# Power.net
KiCad netlist of a schematic drawn in Altium Designer
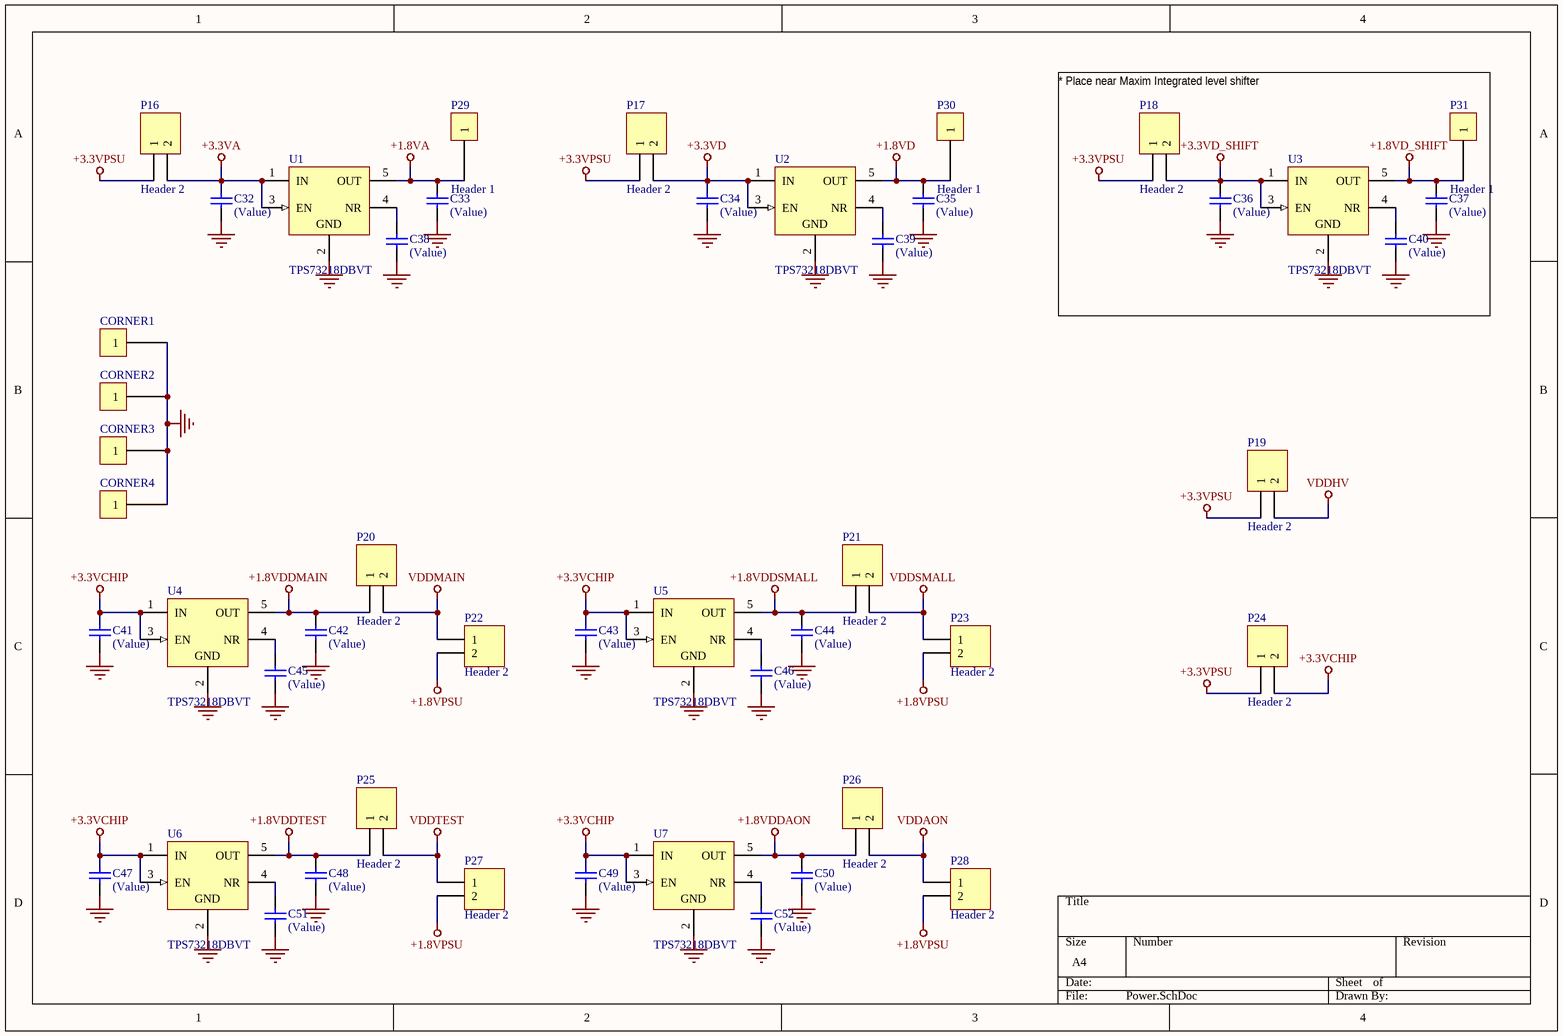
[diagram p0: Power.SchDoc]

(export (version "E")
  (design (tool "Eeschema 10.0.6"))
  (components
    (comp (ref "C32")
      (value "(Value)")
      (footprint "CAPC1608X90X35ML10T15")
      (description "0603")
      (fields (field (name "MANUFACTURER") "Murata"))
      (libsource (lib "Altium Content Vault") (part "CAP-NP-2"))
    )
    (comp (ref "C33")
      (value "(Value)")
      (footprint "CAPC1608X90X35ML10T15")
      (description "0603")
      (fields (field (name "MANUFACTURER") "Murata"))
      (libsource (lib "Altium Content Vault") (part "CAP-NP-2"))
    )
    (comp (ref "C34")
      (value "(Value)")
      (footprint "CAPC1608X90X35ML10T15")
      (description "0603")
      (fields (field (name "MANUFACTURER") "Murata"))
      (libsource (lib "Altium Content Vault") (part "CAP-NP-2"))
    )
    (comp (ref "C35")
      (value "(Value)")
      (footprint "CAPC1608X90X35ML10T15")
      (description "0603")
      (fields (field (name "MANUFACTURER") "Murata"))
      (libsource (lib "Altium Content Vault") (part "CAP-NP-2"))
    )
    (comp (ref "C36")
      (value "(Value)")
      (footprint "CAPC1608X90X35ML10T15")
      (description "0603")
      (fields (field (name "MANUFACTURER") "Murata"))
      (libsource (lib "Altium Content Vault") (part "CAP-NP-2"))
    )
    (comp (ref "C37")
      (value "(Value)")
      (footprint "CAPC1608X90X35ML10T15")
      (description "0603")
      (fields (field (name "MANUFACTURER") "Murata"))
      (libsource (lib "Altium Content Vault") (part "CAP-NP-2"))
    )
    (comp (ref "C38")
      (value "(Value)")
      (footprint "CAPC1608X90X35ML10T15")
      (description "0603")
      (fields (field (name "MANUFACTURER") "Murata"))
      (libsource (lib "Altium Content Vault") (part "CAP-NP-2"))
    )
    (comp (ref "C39")
      (value "(Value)")
      (footprint "CAPC1608X90X35ML10T15")
      (description "0603")
      (fields (field (name "MANUFACTURER") "Murata"))
      (libsource (lib "Altium Content Vault") (part "CAP-NP-2"))
    )
    (comp (ref "C40")
      (value "(Value)")
      (footprint "CAPC1608X90X35ML10T15")
      (description "0603")
      (fields (field (name "MANUFACTURER") "Murata"))
      (libsource (lib "Altium Content Vault") (part "CAP-NP-2"))
    )
    (comp (ref "C41")
      (value "(Value)")
      (footprint "CAPC1608X90X35ML10T15")
      (description "0603")
      (fields (field (name "MANUFACTURER") "Murata"))
      (libsource (lib "Altium Content Vault") (part "CAP-NP-2"))
    )
    (comp (ref "C42")
      (value "(Value)")
      (footprint "CAPC1608X90X35ML10T15")
      (description "0603")
      (fields (field (name "MANUFACTURER") "Murata"))
      (libsource (lib "Altium Content Vault") (part "CAP-NP-2"))
    )
    (comp (ref "C43")
      (value "(Value)")
      (footprint "CAPC1608X90X35ML10T15")
      (description "0603")
      (fields (field (name "MANUFACTURER") "Murata"))
      (libsource (lib "Altium Content Vault") (part "CAP-NP-2"))
    )
    (comp (ref "C44")
      (value "(Value)")
      (footprint "CAPC1608X90X35ML10T15")
      (description "0603")
      (fields (field (name "MANUFACTURER") "Murata"))
      (libsource (lib "Altium Content Vault") (part "CAP-NP-2"))
    )
    (comp (ref "C45")
      (value "(Value)")
      (footprint "CAPC1608X90X35ML10T15")
      (description "0603")
      (fields (field (name "MANUFACTURER") "Murata"))
      (libsource (lib "Altium Content Vault") (part "CAP-NP-2"))
    )
    (comp (ref "C46")
      (value "(Value)")
      (footprint "CAPC1608X90X35ML10T15")
      (description "0603")
      (fields (field (name "MANUFACTURER") "Murata"))
      (libsource (lib "Altium Content Vault") (part "CAP-NP-2"))
    )
    (comp (ref "C47")
      (value "(Value)")
      (footprint "CAPC1608X90X35ML10T15")
      (description "0603")
      (fields (field (name "MANUFACTURER") "Murata"))
      (libsource (lib "Altium Content Vault") (part "CAP-NP-2"))
    )
    (comp (ref "C48")
      (value "(Value)")
      (footprint "CAPC1608X90X35ML10T15")
      (description "0603")
      (fields (field (name "MANUFACTURER") "Murata"))
      (libsource (lib "Altium Content Vault") (part "CAP-NP-2"))
    )
    (comp (ref "C49")
      (value "(Value)")
      (footprint "CAPC1608X90X35ML10T15")
      (description "0603")
      (fields (field (name "MANUFACTURER") "Murata"))
      (libsource (lib "Altium Content Vault") (part "CAP-NP-2"))
    )
    (comp (ref "C50")
      (value "(Value)")
      (footprint "CAPC1608X90X35ML10T15")
      (description "0603")
      (fields (field (name "MANUFACTURER") "Murata"))
      (libsource (lib "Altium Content Vault") (part "CAP-NP-2"))
    )
    (comp (ref "C51")
      (value "(Value)")
      (footprint "CAPC1608X90X35ML10T15")
      (description "0603")
      (fields (field (name "MANUFACTURER") "Murata"))
      (libsource (lib "Altium Content Vault") (part "CAP-NP-2"))
    )
    (comp (ref "C52")
      (value "(Value)")
      (footprint "CAPC1608X90X35ML10T15")
      (description "0603")
      (fields (field (name "MANUFACTURER") "Murata"))
      (libsource (lib "Altium Content Vault") (part "CAP-NP-2"))
    )
    (comp (ref "CORNER1")
      (value "Corner Mount")
      (footprint "CornerMount")
      (libsource (lib "intlib") (part "Corner Mount"))
    )
    (comp (ref "CORNER2")
      (value "Corner Mount")
      (footprint "CornerMount")
      (libsource (lib "intlib") (part "Corner Mount"))
    )
    (comp (ref "CORNER3")
      (value "Corner Mount")
      (footprint "CornerMount")
      (libsource (lib "intlib") (part "Corner Mount"))
    )
    (comp (ref "CORNER4")
      (value "Corner Mount")
      (footprint "CornerMount")
      (libsource (lib "intlib") (part "Corner Mount"))
    )
    (comp (ref "P16")
      (value "Header 2")
      (footprint "HDR1X2")
      (description "Header, 2-Pin")
      (fields (field (name "PUBLISHER") "Altium Limited"))
      (libsource (lib "Miscellaneous Connectors") (part "Header 2"))
    )
    (comp (ref "P17")
      (value "Header 2")
      (footprint "HDR1X2")
      (description "Header, 2-Pin")
      (fields (field (name "PUBLISHER") "Altium Limited"))
      (libsource (lib "Miscellaneous Connectors") (part "Header 2"))
    )
    (comp (ref "P18")
      (value "Header 2")
      (footprint "HDR1X2")
      (description "Header, 2-Pin")
      (fields (field (name "PUBLISHER") "Altium Limited"))
      (libsource (lib "Miscellaneous Connectors") (part "Header 2"))
    )
    (comp (ref "P19")
      (value "Header 2")
      (footprint "HDR1X2")
      (description "Header, 2-Pin")
      (fields (field (name "PUBLISHER") "Altium Limited"))
      (libsource (lib "Miscellaneous Connectors") (part "Header 2"))
    )
    (comp (ref "P20")
      (value "Header 2")
      (footprint "HDR1X2")
      (description "Header, 2-Pin")
      (fields (field (name "PUBLISHER") "Altium Limited"))
      (libsource (lib "Miscellaneous Connectors") (part "Header 2"))
    )
    (comp (ref "P21")
      (value "Header 2")
      (footprint "HDR1X2")
      (description "Header, 2-Pin")
      (fields (field (name "PUBLISHER") "Altium Limited"))
      (libsource (lib "Miscellaneous Connectors") (part "Header 2"))
    )
    (comp (ref "P22")
      (value "Header 2")
      (footprint "HDR1X2")
      (description "Header, 2-Pin")
      (fields (field (name "PUBLISHER") "Altium Limited"))
      (libsource (lib "") (part "Header 2_1"))
    )
    (comp (ref "P23")
      (value "Header 2")
      (footprint "HDR1X2")
      (description "Header, 2-Pin")
      (fields (field (name "PUBLISHER") "Altium Limited"))
      (libsource (lib "") (part "Header 2_1"))
    )
    (comp (ref "P24")
      (value "Header 2")
      (footprint "HDR1X2")
      (description "Header, 2-Pin")
      (fields (field (name "PUBLISHER") "Altium Limited"))
      (libsource (lib "Miscellaneous Connectors") (part "Header 2"))
    )
    (comp (ref "P25")
      (value "Header 2")
      (footprint "HDR1X2")
      (description "Header, 2-Pin")
      (fields (field (name "PUBLISHER") "Altium Limited"))
      (libsource (lib "Miscellaneous Connectors") (part "Header 2"))
    )
    (comp (ref "P26")
      (value "Header 2")
      (footprint "HDR1X2")
      (description "Header, 2-Pin")
      (fields (field (name "PUBLISHER") "Altium Limited"))
      (libsource (lib "Miscellaneous Connectors") (part "Header 2"))
    )
    (comp (ref "P27")
      (value "Header 2")
      (footprint "HDR1X2")
      (description "Header, 2-Pin")
      (fields (field (name "PUBLISHER") "Altium Limited"))
      (libsource (lib "") (part "Header 2_1"))
    )
    (comp (ref "P28")
      (value "Header 2")
      (footprint "HDR1X2")
      (description "Header, 2-Pin")
      (fields (field (name "PUBLISHER") "Altium Limited"))
      (libsource (lib "") (part "Header 2_1"))
    )
    (comp (ref "P29") (value "Header 1") (footprint "Header1") (libsource (lib "intlib") (part "Header 1")))
    (comp (ref "P30") (value "Header 1") (footprint "Header1") (libsource (lib "intlib") (part "Header 1")))
    (comp (ref "P31") (value "Header 1") (footprint "Header1") (libsource (lib "intlib") (part "Header 1")))
    (comp (ref "U1")
      (value "TPS73218DBVT")
      (footprint "DBV0005A_N")
      (fields (field (name "MANUFACTURER") "Texas Instruments"))
      (libsource (lib "Altium Content Vault") (part "TI-TPS79NXX-YYSOT5"))
    )
    (comp (ref "U2")
      (value "TPS73218DBVT")
      (footprint "DBV0005A_N")
      (fields (field (name "MANUFACTURER") "Texas Instruments"))
      (libsource (lib "Altium Content Vault") (part "TI-TPS79NXX-YYSOT5"))
    )
    (comp (ref "U3")
      (value "TPS73218DBVT")
      (footprint "DBV0005A_N")
      (fields (field (name "MANUFACTURER") "Texas Instruments"))
      (libsource (lib "Altium Content Vault") (part "TI-TPS79NXX-YYSOT5"))
    )
    (comp (ref "U4")
      (value "TPS73218DBVT")
      (footprint "DBV0005A_N")
      (fields (field (name "MANUFACTURER") "Texas Instruments"))
      (libsource (lib "Altium Content Vault") (part "TI-TPS79NXX-YYSOT5"))
    )
    (comp (ref "U5")
      (value "TPS73218DBVT")
      (footprint "DBV0005A_N")
      (fields (field (name "MANUFACTURER") "Texas Instruments"))
      (libsource (lib "Altium Content Vault") (part "TI-TPS79NXX-YYSOT5"))
    )
    (comp (ref "U6")
      (value "TPS73218DBVT")
      (footprint "DBV0005A_N")
      (fields (field (name "MANUFACTURER") "Texas Instruments"))
      (libsource (lib "Altium Content Vault") (part "TI-TPS79NXX-YYSOT5"))
    )
    (comp (ref "U7")
      (value "TPS73218DBVT")
      (footprint "DBV0005A_N")
      (fields (field (name "MANUFACTURER") "Texas Instruments"))
      (libsource (lib "Altium Content Vault") (part "TI-TPS79NXX-YYSOT5"))
    )
  )
  (nets
    (net (code "1") (name "+1.8VA") (class "Default")
      (node (ref "C33") (pin "1") (pinfunction "1_1") (pintype "passive"))
      (node (ref "P29") (pin "1") (pinfunction "1_1") (pintype "passive"))
      (node (ref "U1") (pin "5") (pinfunction "OUT_5") (pintype "power_in"))
    )
    (net (code "2") (name "+1.8VD") (class "Default")
      (node (ref "C35") (pin "1") (pinfunction "1_1") (pintype "passive"))
      (node (ref "P30") (pin "1") (pinfunction "1_1") (pintype "passive"))
      (node (ref "U2") (pin "5") (pinfunction "OUT_5") (pintype "power_in"))
    )
    (net (code "3") (name "+1.8VDDAON") (class "Default")
      (node (ref "C50") (pin "1") (pinfunction "1_1") (pintype "passive"))
      (node (ref "P26") (pin "1") (pinfunction "1_1") (pintype "passive"))
      (node (ref "U7") (pin "5") (pinfunction "OUT_5") (pintype "power_in"))
    )
    (net (code "4") (name "+1.8VDDMAIN") (class "Default")
      (node (ref "C42") (pin "1") (pinfunction "1_1") (pintype "passive"))
      (node (ref "P20") (pin "1") (pinfunction "1_1") (pintype "passive"))
      (node (ref "U4") (pin "5") (pinfunction "OUT_5") (pintype "power_in"))
    )
    (net (code "5") (name "+1.8VDDSMALL") (class "Default")
      (node (ref "C44") (pin "1") (pinfunction "1_1") (pintype "passive"))
      (node (ref "P21") (pin "1") (pinfunction "1_1") (pintype "passive"))
      (node (ref "U5") (pin "5") (pinfunction "OUT_5") (pintype "power_in"))
    )
    (net (code "6") (name "+1.8VDDTEST") (class "Default")
      (node (ref "C48") (pin "1") (pinfunction "1_1") (pintype "passive"))
      (node (ref "P25") (pin "1") (pinfunction "1_1") (pintype "passive"))
      (node (ref "U6") (pin "5") (pinfunction "OUT_5") (pintype "power_in"))
    )
    (net (code "7") (name "+1.8VD_SHIFT") (class "Default")
      (node (ref "C37") (pin "1") (pinfunction "1_1") (pintype "passive"))
      (node (ref "P31") (pin "1") (pinfunction "1_1") (pintype "passive"))
      (node (ref "U3") (pin "5") (pinfunction "OUT_5") (pintype "power_in"))
    )
    (net (code "8") (name "+1.8VPSU") (class "Default")
      (node (ref "P22") (pin "2") (pinfunction "2_2") (pintype "passive"))
      (node (ref "P23") (pin "2") (pinfunction "2_2") (pintype "passive"))
      (node (ref "P27") (pin "2") (pinfunction "2_2") (pintype "passive"))
      (node (ref "P28") (pin "2") (pinfunction "2_2") (pintype "passive"))
    )
    (net (code "9") (name "+3.3VA") (class "Default")
      (node (ref "C32") (pin "1") (pinfunction "1_1") (pintype "passive"))
      (node (ref "P16") (pin "2") (pinfunction "2_2") (pintype "passive"))
      (node (ref "U1") (pin "1") (pinfunction "IN_1") (pintype "power_in"))
      (node (ref "U1") (pin "3") (pinfunction "EN_3") (pintype "input"))
    )
    (net (code "10") (name "+3.3VCHIP") (class "Default")
      (node (ref "C41") (pin "1") (pinfunction "1_1") (pintype "passive"))
      (node (ref "C43") (pin "1") (pinfunction "1_1") (pintype "passive"))
      (node (ref "C47") (pin "1") (pinfunction "1_1") (pintype "passive"))
      (node (ref "C49") (pin "1") (pinfunction "1_1") (pintype "passive"))
      (node (ref "P24") (pin "2") (pinfunction "2_2") (pintype "passive"))
      (node (ref "U4") (pin "1") (pinfunction "IN_1") (pintype "power_in"))
      (node (ref "U4") (pin "3") (pinfunction "EN_3") (pintype "input"))
      (node (ref "U5") (pin "1") (pinfunction "IN_1") (pintype "power_in"))
      (node (ref "U5") (pin "3") (pinfunction "EN_3") (pintype "input"))
      (node (ref "U6") (pin "1") (pinfunction "IN_1") (pintype "power_in"))
      (node (ref "U6") (pin "3") (pinfunction "EN_3") (pintype "input"))
      (node (ref "U7") (pin "1") (pinfunction "IN_1") (pintype "power_in"))
      (node (ref "U7") (pin "3") (pinfunction "EN_3") (pintype "input"))
    )
    (net (code "11") (name "+3.3VD") (class "Default")
      (node (ref "C34") (pin "1") (pinfunction "1_1") (pintype "passive"))
      (node (ref "P17") (pin "2") (pinfunction "2_2") (pintype "passive"))
      (node (ref "U2") (pin "1") (pinfunction "IN_1") (pintype "power_in"))
      (node (ref "U2") (pin "3") (pinfunction "EN_3") (pintype "input"))
    )
    (net (code "12") (name "+3.3VD_SHIFT") (class "Default")
      (node (ref "C36") (pin "1") (pinfunction "1_1") (pintype "passive"))
      (node (ref "P18") (pin "2") (pinfunction "2_2") (pintype "passive"))
      (node (ref "U3") (pin "1") (pinfunction "IN_1") (pintype "power_in"))
      (node (ref "U3") (pin "3") (pinfunction "EN_3") (pintype "input"))
    )
    (net (code "13") (name "+3.3VPSU") (class "Default")
      (node (ref "P16") (pin "1") (pinfunction "1_1") (pintype "passive"))
      (node (ref "P17") (pin "1") (pinfunction "1_1") (pintype "passive"))
      (node (ref "P18") (pin "1") (pinfunction "1_1") (pintype "passive"))
      (node (ref "P19") (pin "1") (pinfunction "1_1") (pintype "passive"))
      (node (ref "P24") (pin "1") (pinfunction "1_1") (pintype "passive"))
    )
    (net (code "14") (name "GND") (class "Default")
      (node (ref "C32") (pin "2") (pinfunction "2_2") (pintype "passive"))
      (node (ref "C33") (pin "2") (pinfunction "2_2") (pintype "passive"))
      (node (ref "C34") (pin "2") (pinfunction "2_2") (pintype "passive"))
      (node (ref "C35") (pin "2") (pinfunction "2_2") (pintype "passive"))
      (node (ref "C36") (pin "2") (pinfunction "2_2") (pintype "passive"))
      (node (ref "C37") (pin "2") (pinfunction "2_2") (pintype "passive"))
      (node (ref "C38") (pin "2") (pinfunction "2_2") (pintype "passive"))
      (node (ref "C39") (pin "2") (pinfunction "2_2") (pintype "passive"))
      (node (ref "C40") (pin "2") (pinfunction "2_2") (pintype "passive"))
      (node (ref "C41") (pin "2") (pinfunction "2_2") (pintype "passive"))
      (node (ref "C42") (pin "2") (pinfunction "2_2") (pintype "passive"))
      (node (ref "C43") (pin "2") (pinfunction "2_2") (pintype "passive"))
      (node (ref "C44") (pin "2") (pinfunction "2_2") (pintype "passive"))
      (node (ref "C45") (pin "2") (pinfunction "2_2") (pintype "passive"))
      (node (ref "C46") (pin "2") (pinfunction "2_2") (pintype "passive"))
      (node (ref "C47") (pin "2") (pinfunction "2_2") (pintype "passive"))
      (node (ref "C48") (pin "2") (pinfunction "2_2") (pintype "passive"))
      (node (ref "C49") (pin "2") (pinfunction "2_2") (pintype "passive"))
      (node (ref "C50") (pin "2") (pinfunction "2_2") (pintype "passive"))
      (node (ref "C51") (pin "2") (pinfunction "2_2") (pintype "passive"))
      (node (ref "C52") (pin "2") (pinfunction "2_2") (pintype "passive"))
      (node (ref "CORNER1") (pin "1") (pinfunction "1_1") (pintype "passive"))
      (node (ref "CORNER2") (pin "1") (pinfunction "1_1") (pintype "passive"))
      (node (ref "CORNER3") (pin "1") (pinfunction "1_1") (pintype "passive"))
      (node (ref "CORNER4") (pin "1") (pinfunction "1_1") (pintype "passive"))
      (node (ref "U1") (pin "2") (pinfunction "GND_2") (pintype "power_in"))
      (node (ref "U2") (pin "2") (pinfunction "GND_2") (pintype "power_in"))
      (node (ref "U3") (pin "2") (pinfunction "GND_2") (pintype "power_in"))
      (node (ref "U4") (pin "2") (pinfunction "GND_2") (pintype "power_in"))
      (node (ref "U5") (pin "2") (pinfunction "GND_2") (pintype "power_in"))
      (node (ref "U6") (pin "2") (pinfunction "GND_2") (pintype "power_in"))
      (node (ref "U7") (pin "2") (pinfunction "GND_2") (pintype "power_in"))
    )
    (net (code "15") (name "Net-(U1-NR)") (class "Default")
      (node (ref "C38") (pin "1") (pinfunction "1_1") (pintype "passive"))
      (node (ref "U1") (pin "4") (pinfunction "NR_4") (pintype "passive"))
    )
    (net (code "16") (name "Net-(U2-NR)") (class "Default")
      (node (ref "C39") (pin "1") (pinfunction "1_1") (pintype "passive"))
      (node (ref "U2") (pin "4") (pinfunction "NR_4") (pintype "passive"))
    )
    (net (code "17") (name "Net-(U3-NR)") (class "Default")
      (node (ref "C40") (pin "1") (pinfunction "1_1") (pintype "passive"))
      (node (ref "U3") (pin "4") (pinfunction "NR_4") (pintype "passive"))
    )
    (net (code "18") (name "Net-(U4-NR)") (class "Default")
      (node (ref "C45") (pin "1") (pinfunction "1_1") (pintype "passive"))
      (node (ref "U4") (pin "4") (pinfunction "NR_4") (pintype "passive"))
    )
    (net (code "19") (name "Net-(U5-NR)") (class "Default")
      (node (ref "C46") (pin "1") (pinfunction "1_1") (pintype "passive"))
      (node (ref "U5") (pin "4") (pinfunction "NR_4") (pintype "passive"))
    )
    (net (code "20") (name "Net-(U6-NR)") (class "Default")
      (node (ref "C51") (pin "1") (pinfunction "1_1") (pintype "passive"))
      (node (ref "U6") (pin "4") (pinfunction "NR_4") (pintype "passive"))
    )
    (net (code "21") (name "Net-(U7-NR)") (class "Default")
      (node (ref "C52") (pin "1") (pinfunction "1_1") (pintype "passive"))
      (node (ref "U7") (pin "4") (pinfunction "NR_4") (pintype "passive"))
    )
    (net (code "22") (name "VDDAON") (class "Default")
      (node (ref "P26") (pin "2") (pinfunction "2_2") (pintype "passive"))
      (node (ref "P28") (pin "1") (pinfunction "1_1") (pintype "passive"))
    )
    (net (code "23") (name "VDDHV") (class "Default")
      (node (ref "P19") (pin "2") (pinfunction "2_2") (pintype "passive"))
    )
    (net (code "24") (name "VDDMAIN") (class "Default")
      (node (ref "P20") (pin "2") (pinfunction "2_2") (pintype "passive"))
      (node (ref "P22") (pin "1") (pinfunction "1_1") (pintype "passive"))
    )
    (net (code "25") (name "VDDSMALL") (class "Default")
      (node (ref "P21") (pin "2") (pinfunction "2_2") (pintype "passive"))
      (node (ref "P23") (pin "1") (pinfunction "1_1") (pintype "passive"))
    )
    (net (code "26") (name "VDDTEST") (class "Default")
      (node (ref "P25") (pin "2") (pinfunction "2_2") (pintype "passive"))
      (node (ref "P27") (pin "1") (pinfunction "1_1") (pintype "passive"))
    )
  )
)
